# Digital_Sensors.net
KiCad netlist of a schematic drawn in Altium Designer
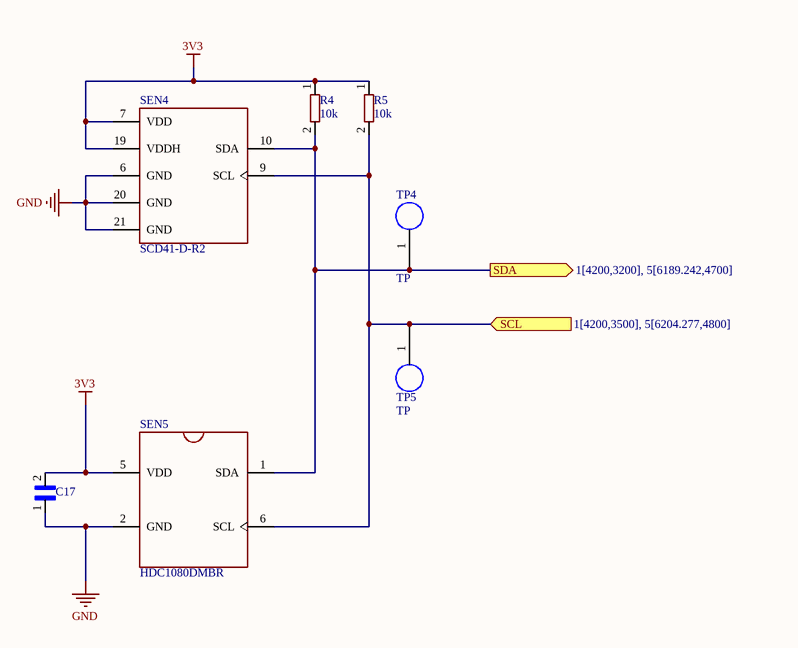
[diagram p0: Digital Sensors.SchDoc]

(export (version "E")
  (design (tool "Eeschema 10.0.6"))
  (components
    (comp (ref "C17")
      (value "CC1206JRX7R9BB104")
      (footprint "0.1uF Capacitor")
      (description "No Description Available")
      (libsource (lib "0.1uF Capacitor") (part "CC1206JRX7R9BB104"))
    )
    (comp (ref "R4")
      (value "10k")
      (footprint "10K Resistor:0603")
      (description "http://octopart.com/rc0603fr-1310kl-yageo+%2F+phycomp-25905087")
      (fields (field (name "MP") "RC0603FR-1310KL"))
      (libsource (lib "10K Resistor") (part "RC0603FR-1310KL"))
    )
    (comp (ref "R5")
      (value "10k")
      (footprint "10K Resistor:0603")
      (description "http://octopart.com/rc0603fr-1310kl-yageo+%2F+phycomp-25905087")
      (fields (field (name "MP") "RC0603FR-1310KL"))
      (libsource (lib "10K Resistor") (part "RC0603FR-1310KL"))
    )
    (comp (ref "SEN4")
      (value "SCD41-D-R2")
      (footprint "XDCR_SCD41-D-R2")
      (description "Air Quality Sensor CO2 Sensor 2.5V/3.3V/5V 20-Pin SMD EP")
      (fields (field (name "MF") "Sensirion AG"))
      (libsource (lib "CO2 Sensor") (part "SCD41-D-R2"))
    )
    (comp (ref "SEN5")
      (value "HDC1080DMBR")
      (footprint "Temp Sensor:SON100P300X300X80-7N")
      (description "Temperature and Humidity Sensor")
      (fields (field (name "MF") "Texas Instruments"))
      (libsource (lib "Temp Sensor") (part "HDC1080DMBR"))
    )
    (comp (ref "TP4")
      (value "TP")
      (footprint "TestPoint")
      (description "Test point for voltage, current, ect.")
      (libsource (lib "TestPoint") (part "TestPoint"))
    )
    (comp (ref "TP5")
      (value "TP")
      (footprint "TestPoint")
      (description "Test point for voltage, current, ect.")
      (libsource (lib "TestPoint") (part "TestPoint"))
    )
  )
  (nets
    (net (code "1") (name "/SCL") (class "Default")
      (node (ref "R5") (pin "2") (pintype "passive"))
      (node (ref "SEN4") (pin "9") (pinfunction "SCL_9") (pintype "passive"))
      (node (ref "SEN5") (pin "6") (pinfunction "SCL_6") (pintype "passive"))
      (node (ref "TP5") (pin "1") (pintype "passive"))
    )
    (net (code "2") (name "/SDA") (class "Default")
      (node (ref "R4") (pin "2") (pintype "passive"))
      (node (ref "SEN4") (pin "10") (pinfunction "SDA_10") (pintype "passive"))
      (node (ref "SEN5") (pin "1") (pinfunction "SDA_1") (pintype "passive"))
      (node (ref "TP4") (pin "1") (pintype "passive"))
    )
    (net (code "3") (name "3V3") (class "Default")
      (node (ref "C17") (pin "2") (pintype "passive"))
      (node (ref "R4") (pin "1") (pintype "passive"))
      (node (ref "R5") (pin "1") (pintype "passive"))
      (node (ref "SEN4") (pin "19") (pinfunction "VDDH_19") (pintype "power_in"))
      (node (ref "SEN4") (pin "7") (pinfunction "VDD_7") (pintype "power_in"))
      (node (ref "SEN5") (pin "5") (pinfunction "VDD_5") (pintype "power_in"))
    )
    (net (code "4") (name "GND") (class "Default")
      (node (ref "C17") (pin "1") (pintype "passive"))
      (node (ref "SEN4") (pin "20") (pinfunction "GND_20") (pintype "power_in"))
      (node (ref "SEN4") (pin "21") (pinfunction "GND_21") (pintype "power_in"))
      (node (ref "SEN4") (pin "6") (pinfunction "GND_6") (pintype "power_in"))
      (node (ref "SEN5") (pin "2") (pinfunction "GND_2") (pintype "power_in"))
    )
  )
)
